# edge.net
KiCad netlist of a schematic drawn in EAGLE
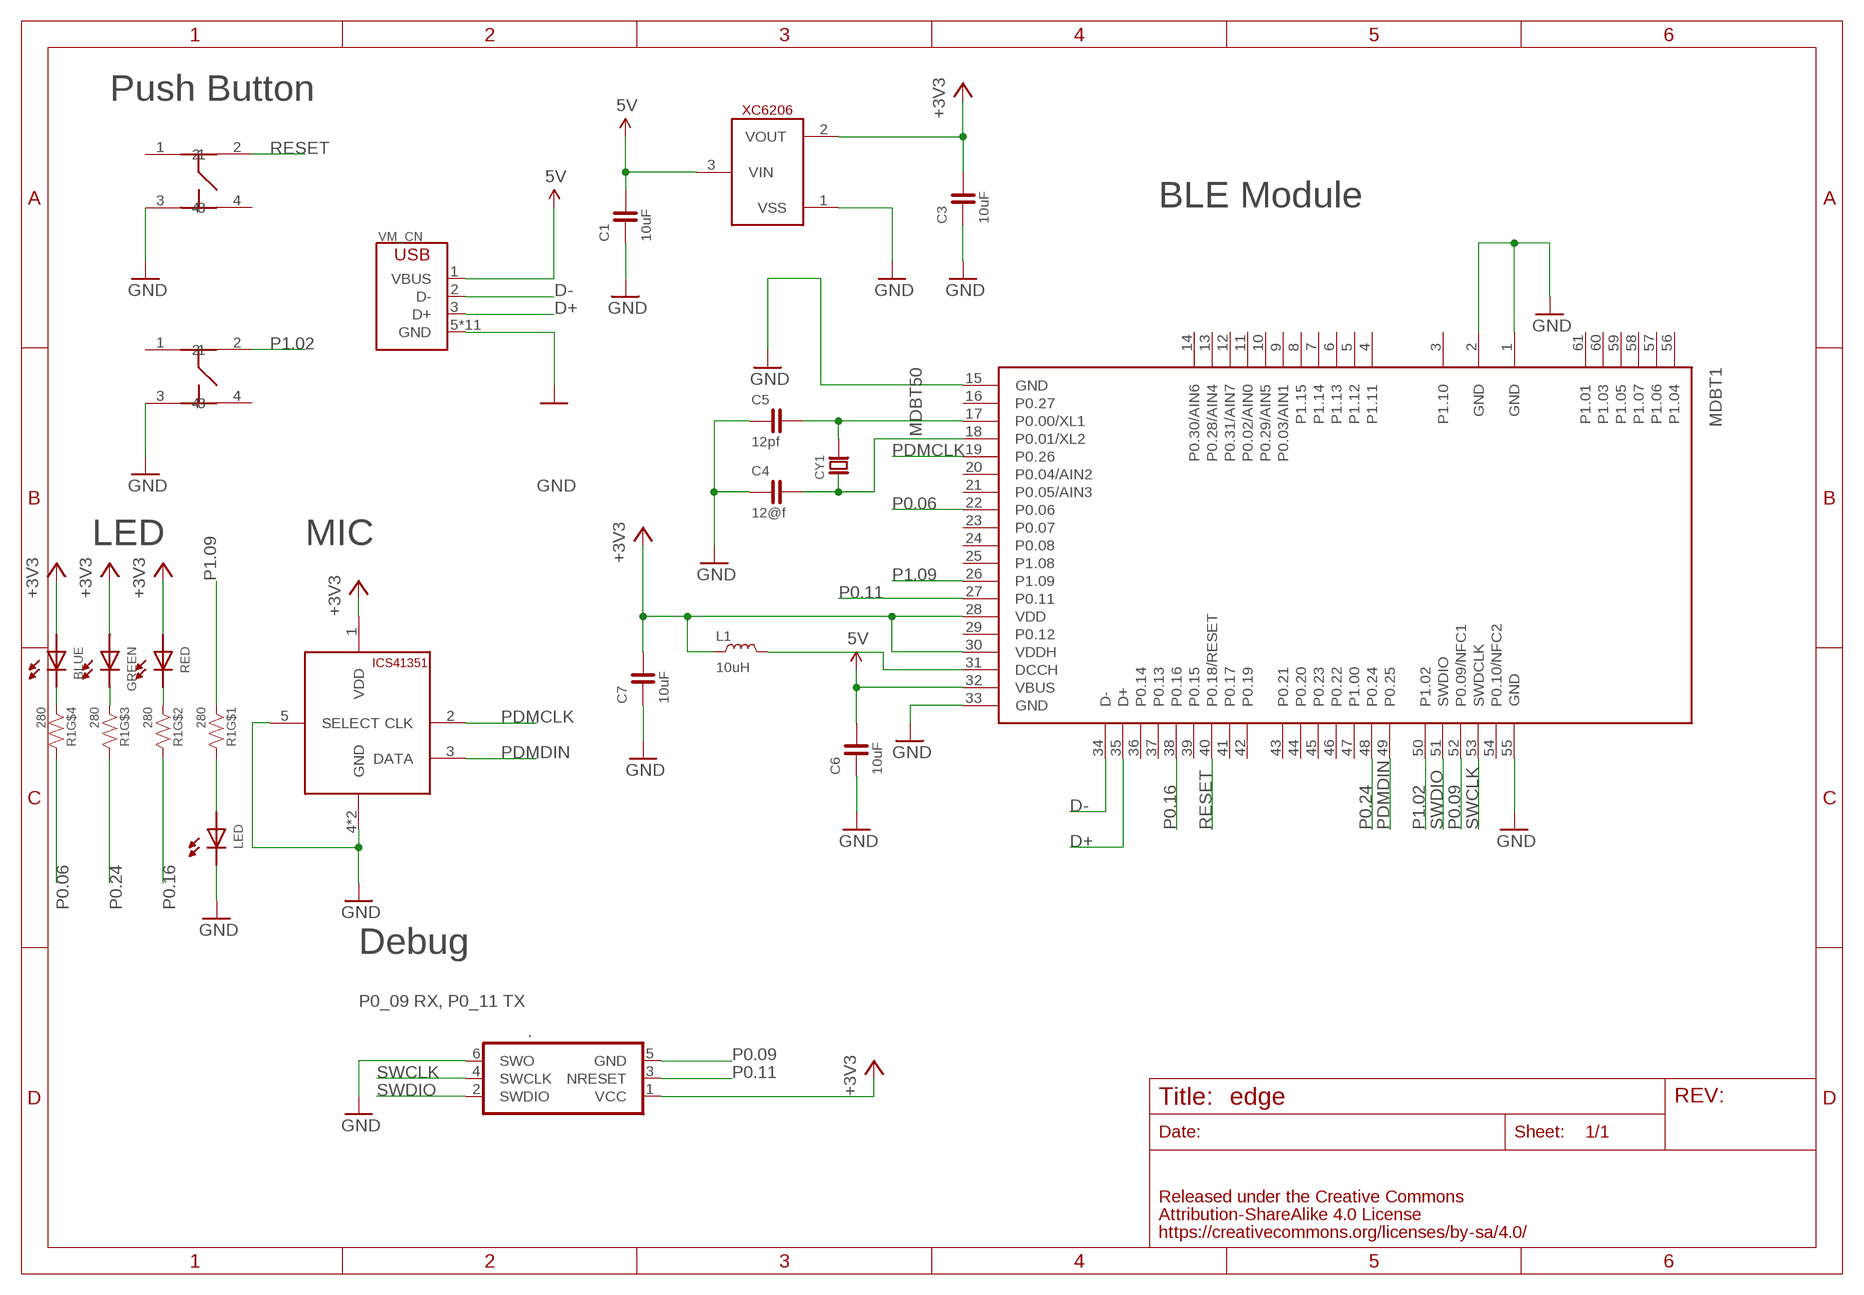
[diagram p0: schematic, sheet 1]

(export (version "E")
  (design (tool "Eeschema 10.0.6"))
  (components
    (comp (ref ".")
      (value "TC2030-IDC-NL")
      (footprint "eagle-import:TC2030-IDC-NL")
      (libsource (lib "eagle-import") (part "TC2030-IDC-NL"))
    )
    (comp (ref "BLUE")
      (value "LED-0603")
      (footprint "eagle-import:0603")
      (libsource (lib "eagle-import") (part "LED-0603"))
    )
    (comp (ref "C1")
      (value "10uF")
      (footprint "eagle-import:0603")
      (libsource (lib "eagle-import") (part "CAPACITOR-0603"))
    )
    (comp (ref "C3")
      (value "10uF")
      (footprint "eagle-import:0603")
      (libsource (lib "eagle-import") (part "CAPACITOR-0603"))
    )
    (comp (ref "C4")
      (value "12@f")
      (footprint "eagle-import:0603")
      (libsource (lib "eagle-import") (part "CAPACITOR-0603"))
    )
    (comp (ref "C5")
      (value "12pf")
      (footprint "eagle-import:0603")
      (libsource (lib "eagle-import") (part "CAPACITOR-0603"))
    )
    (comp (ref "C6")
      (value "10uF")
      (footprint "eagle-import:0603")
      (libsource (lib "eagle-import") (part "CAPACITOR-0603"))
    )
    (comp (ref "C7")
      (value "10uF")
      (footprint "eagle-import:0603")
      (libsource (lib "eagle-import") (part "CAPACITOR-0603"))
    )
    (comp (ref "CY1")
      (value "CRYSTAL-ABS07")
      (footprint "eagle-import:ABRACON-ABS07-32.768KHZ")
      (libsource (lib "eagle-import") (part "CRYSTAL-ABS07"))
    )
    (comp (ref "GREEN")
      (value "LED-0603")
      (footprint "eagle-import:0603")
      (libsource (lib "eagle-import") (part "LED-0603"))
    )
    (comp (ref "IC1")
      (value "XC6206")
      (footprint "eagle-import:SOT-23")
      (libsource (lib "eagle-import") (part "XC6206"))
    )
    (comp (ref "L1")
      (value "10uH")
      (footprint "eagle-import:0603")
      (libsource (lib "eagle-import") (part "COIL-0603"))
    )
    (comp (ref "LED")
      (value "LED-0603")
      (footprint "eagle-import:0603")
      (libsource (lib "eagle-import") (part "LED-0603"))
    )
    (comp (ref "MDBT1")
      (value "MDBT50")
      (footprint "eagle-import:MDBT50")
      (libsource (lib "eagle-import") (part "MDBT50"))
    )
    (comp (ref "MIC1")
      (value "TDK-ICS41351")
      (footprint "eagle-import:ICS41351")
      (libsource (lib "eagle-import") (part "TDK-ICS41351"))
    )
    (comp (ref "R1")
      (value "280")
      (footprint "eagle-import:EXBV8V")
      (libsource (lib "eagle-import") (part "RESISTOR_ARRAY"))
    )
    (comp (ref "RED")
      (value "LED-0603")
      (footprint "eagle-import:0603")
      (libsource (lib "eagle-import") (part "LED-0603"))
    )
    (comp (ref "U$1")
      (value "SWICTH-4P(KMR2)")
      (footprint "eagle-import:SWITCH-4P(KMR2)")
      (libsource (lib "eagle-import") (part "SWICTH-4P(KMR2)"))
    )
    (comp (ref "U$5")
      (value "SWICTH-4P(KMR2)")
      (footprint "eagle-import:SWITCH-4P(KMR2)")
      (libsource (lib "eagle-import") (part "SWICTH-4P(KMR2)"))
    )
    (comp (ref "VM_CN")
      (value "USB-ZX62D")
      (footprint "eagle-import:ZX62D-B-5PA8")
      (libsource (lib "eagle-import") (part "USB-ZX62D"))
    )
  )
  (nets
    (net (code "1") (name "+3V3") (class "Default")
      (node (ref ".") (pin "1") (pinfunction "VCC_1") (pintype "passive"))
      (node (ref "BLUE") (pin "ANODE") (pinfunction "ANODE_ANODE") (pintype "passive"))
      (node (ref "C3") (pin "2") (pinfunction "2_2") (pintype "passive"))
      (node (ref "C7") (pin "2") (pinfunction "2_2") (pintype "passive"))
      (node (ref "GREEN") (pin "ANODE") (pinfunction "ANODE_ANODE") (pintype "passive"))
      (node (ref "IC1") (pin "2") (pinfunction "VOUT_2") (pintype "bidirectional"))
      (node (ref "L1") (pin "1") (pinfunction "1_1") (pintype "bidirectional"))
      (node (ref "MDBT1") (pin "28") (pinfunction "VDD_28") (pintype "bidirectional"))
      (node (ref "MDBT1") (pin "30") (pinfunction "VDDH_30") (pintype "bidirectional"))
      (node (ref "MIC1") (pin "1") (pinfunction "VDD_1") (pintype "bidirectional"))
      (node (ref "RED") (pin "ANODE") (pinfunction "ANODE_ANODE") (pintype "passive"))
    )
    (net (code "2") (name "/D+") (class "Default")
      (node (ref "MDBT1") (pin "35") (pinfunction "D+_35") (pintype "bidirectional"))
      (node (ref "VM_CN") (pin "3") (pinfunction "D+_3") (pintype "bidirectional"))
    )
    (net (code "3") (name "/D-") (class "Default")
      (node (ref "MDBT1") (pin "34") (pinfunction "D-_34") (pintype "bidirectional"))
      (node (ref "VM_CN") (pin "2") (pinfunction "D-_2") (pintype "bidirectional"))
    )
    (net (code "4") (name "/P0.06") (class "Default")
      (node (ref "MDBT1") (pin "22") (pinfunction "P0.06_22") (pintype "bidirectional"))
      (node (ref "R1") (pin "5") (pinfunction "2_5") (pintype "bidirectional"))
    )
    (net (code "5") (name "/P0.09") (class "Default")
      (node (ref ".") (pin "5") (pinfunction "GND_5") (pintype "passive"))
      (node (ref "MDBT1") (pin "52") (pinfunction "P0.09/NFC1_52") (pintype "bidirectional"))
    )
    (net (code "6") (name "/P0.11") (class "Default")
      (node (ref ".") (pin "3") (pinfunction "NRESET_3") (pintype "passive"))
      (node (ref "MDBT1") (pin "27") (pinfunction "P0.11_27") (pintype "bidirectional"))
    )
    (net (code "7") (name "/P0.16") (class "Default")
      (node (ref "MDBT1") (pin "38") (pinfunction "P0.16_38") (pintype "bidirectional"))
      (node (ref "R1") (pin "7") (pinfunction "2_7") (pintype "bidirectional"))
    )
    (net (code "8") (name "/P0.24") (class "Default")
      (node (ref "MDBT1") (pin "48") (pinfunction "P0.24_48") (pintype "bidirectional"))
      (node (ref "R1") (pin "6") (pinfunction "2_6") (pintype "bidirectional"))
    )
    (net (code "9") (name "/P1.02") (class "Default")
      (node (ref "MDBT1") (pin "50") (pinfunction "P1.02_50") (pintype "bidirectional"))
      (node (ref "U$1") (pin "2") (pinfunction "2_2") (pintype "bidirectional"))
    )
    (net (code "10") (name "/P1.09") (class "Default")
      (node (ref "MDBT1") (pin "26") (pinfunction "P1.09_26") (pintype "bidirectional"))
      (node (ref "R1") (pin "1") (pinfunction "1_1") (pintype "bidirectional"))
    )
    (net (code "11") (name "/PDMCLK") (class "Default")
      (node (ref "MDBT1") (pin "19") (pinfunction "P0.26_19") (pintype "bidirectional"))
      (node (ref "MIC1") (pin "2") (pinfunction "CLK_2") (pintype "bidirectional"))
    )
    (net (code "12") (name "/PDMDIN") (class "Default")
      (node (ref "MDBT1") (pin "49") (pinfunction "P0.25_49") (pintype "bidirectional"))
      (node (ref "MIC1") (pin "3") (pinfunction "DATA_3") (pintype "bidirectional"))
    )
    (net (code "13") (name "/RESET") (class "Default")
      (node (ref "MDBT1") (pin "40") (pinfunction "P0.18/RESET_40") (pintype "bidirectional"))
      (node (ref "U$5") (pin "2") (pinfunction "2_2") (pintype "bidirectional"))
    )
    (net (code "14") (name "/SWCLK") (class "Default")
      (node (ref ".") (pin "4") (pinfunction "SWCLK_4") (pintype "passive"))
      (node (ref "MDBT1") (pin "53") (pinfunction "SWDCLK_53") (pintype "bidirectional"))
    )
    (net (code "15") (name "/SWDIO") (class "Default")
      (node (ref ".") (pin "2") (pinfunction "SWDIO_2") (pintype "passive"))
      (node (ref "MDBT1") (pin "51") (pinfunction "SWDIO_51") (pintype "bidirectional"))
    )
    (net (code "16") (name "5V") (class "Default")
      (node (ref "C1") (pin "2") (pinfunction "2_2") (pintype "passive"))
      (node (ref "C6") (pin "2") (pinfunction "2_2") (pintype "passive"))
      (node (ref "IC1") (pin "3") (pinfunction "VIN_3") (pintype "bidirectional"))
      (node (ref "MDBT1") (pin "32") (pinfunction "VBUS_32") (pintype "bidirectional"))
      (node (ref "VM_CN") (pin "1") (pinfunction "VBUS_1") (pintype "bidirectional"))
    )
    (net (code "17") (name "GND") (class "Default")
      (node (ref ".") (pin "6") (pinfunction "SWO_6") (pintype "passive"))
      (node (ref "C1") (pin "1") (pinfunction "1_1") (pintype "passive"))
      (node (ref "C3") (pin "1") (pinfunction "1_1") (pintype "passive"))
      (node (ref "C4") (pin "1") (pinfunction "1_1") (pintype "passive"))
      (node (ref "C5") (pin "1") (pinfunction "1_1") (pintype "passive"))
      (node (ref "C6") (pin "1") (pinfunction "1_1") (pintype "passive"))
      (node (ref "C7") (pin "1") (pinfunction "1_1") (pintype "passive"))
      (node (ref "IC1") (pin "1") (pinfunction "VSS_1") (pintype "bidirectional"))
      (node (ref "LED") (pin "CATHODE") (pinfunction "CATHODE_CATHODE") (pintype "passive"))
      (node (ref "MDBT1") (pin "1") (pinfunction "GND_1") (pintype "bidirectional"))
      (node (ref "MDBT1") (pin "15") (pinfunction "GND_15") (pintype "bidirectional"))
      (node (ref "MDBT1") (pin "2") (pinfunction "GND_2") (pintype "bidirectional"))
      (node (ref "MDBT1") (pin "33") (pinfunction "GND_33") (pintype "bidirectional"))
      (node (ref "MDBT1") (pin "55") (pinfunction "GND_55") (pintype "bidirectional"))
      (node (ref "MIC1") (pin "4") (pinfunction "GND_4") (pintype "bidirectional"))
      (node (ref "MIC1") (pin "5") (pinfunction "SELECT_5") (pintype "bidirectional"))
      (node (ref "MIC1") (pin "6") (pinfunction "GND_6") (pintype "bidirectional"))
      (node (ref "U$1") (pin "3") (pinfunction "3_3") (pintype "bidirectional"))
      (node (ref "U$5") (pin "3") (pinfunction "3_3") (pintype "bidirectional"))
      (node (ref "VM_CN") (pin "5") (pinfunction "GND_5") (pintype "bidirectional"))
      (node (ref "VM_CN") (pin "B1") (pinfunction "GND_B1") (pintype "bidirectional"))
      (node (ref "VM_CN") (pin "B2") (pinfunction "GND_B2") (pintype "bidirectional"))
      (node (ref "VM_CN") (pin "B3") (pinfunction "GND_B3") (pintype "bidirectional"))
      (node (ref "VM_CN") (pin "B4") (pinfunction "GND_B4") (pintype "bidirectional"))
      (node (ref "VM_CN") (pin "T1") (pinfunction "GND_T1") (pintype "bidirectional"))
      (node (ref "VM_CN") (pin "T2") (pinfunction "GND_T2") (pintype "bidirectional"))
      (node (ref "VM_CN") (pin "T3") (pinfunction "GND_T3") (pintype "bidirectional"))
      (node (ref "VM_CN") (pin "T4") (pinfunction "GND_T4") (pintype "bidirectional"))
      (node (ref "VM_CN") (pin "T5") (pinfunction "GND_T5") (pintype "bidirectional"))
      (node (ref "VM_CN") (pin "T6") (pinfunction "GND_T6") (pintype "bidirectional"))
    )
    (net (code "18") (name "Net-(MDBT1-DCCH)") (class "Default")
      (node (ref "L1") (pin "2") (pinfunction "2_2") (pintype "bidirectional"))
      (node (ref "MDBT1") (pin "31") (pinfunction "DCCH_31") (pintype "bidirectional"))
    )
    (net (code "19") (name "Net-(MDBT1-P0.00{slash}XL1)") (class "Default")
      (node (ref "C5") (pin "2") (pinfunction "2_2") (pintype "passive"))
      (node (ref "CY1") (pin "P$2") (pinfunction "P$2_P$2") (pintype "bidirectional"))
      (node (ref "MDBT1") (pin "17") (pinfunction "P0.00/XL1_17") (pintype "bidirectional"))
    )
    (net (code "20") (name "Net-(MDBT1-P0.01{slash}XL2)") (class "Default")
      (node (ref "C4") (pin "2") (pinfunction "2_2") (pintype "passive"))
      (node (ref "CY1") (pin "P$1") (pinfunction "P$1_P$1") (pintype "bidirectional"))
      (node (ref "MDBT1") (pin "18") (pinfunction "P0.01/XL2_18") (pintype "bidirectional"))
    )
    (net (code "21") (name "Net-(R1A-2)") (class "Default")
      (node (ref "LED") (pin "ANODE") (pinfunction "ANODE_ANODE") (pintype "passive"))
      (node (ref "R1") (pin "8") (pinfunction "2_8") (pintype "bidirectional"))
    )
    (net (code "22") (name "Net-(R1B-1)") (class "Default")
      (node (ref "R1") (pin "2") (pinfunction "1_2") (pintype "bidirectional"))
      (node (ref "RED") (pin "CATHODE") (pinfunction "CATHODE_CATHODE") (pintype "passive"))
    )
    (net (code "23") (name "Net-(R1C-1)") (class "Default")
      (node (ref "GREEN") (pin "CATHODE") (pinfunction "CATHODE_CATHODE") (pintype "passive"))
      (node (ref "R1") (pin "3") (pinfunction "1_3") (pintype "bidirectional"))
    )
    (net (code "24") (name "Net-(R1D-1)") (class "Default")
      (node (ref "BLUE") (pin "CATHODE") (pinfunction "CATHODE_CATHODE") (pintype "passive"))
      (node (ref "R1") (pin "4") (pinfunction "1_4") (pintype "bidirectional"))
    )
    (net (code "25") (name "unconnected-(MDBT1-P0.02{slash}AIN0-Pad11)") (class "Default")
      (node (ref "MDBT1") (pin "11") (pinfunction "P0.02/AIN0_11") (pintype "bidirectional"))
    )
    (net (code "26") (name "unconnected-(MDBT1-P0.03{slash}AIN1-Pad9)") (class "Default")
      (node (ref "MDBT1") (pin "9") (pinfunction "P0.03/AIN1_9") (pintype "bidirectional"))
    )
    (net (code "27") (name "unconnected-(MDBT1-P0.04{slash}AIN2-Pad20)") (class "Default")
      (node (ref "MDBT1") (pin "20") (pinfunction "P0.04/AIN2_20") (pintype "bidirectional"))
    )
    (net (code "28") (name "unconnected-(MDBT1-P0.05{slash}AIN3-Pad21)") (class "Default")
      (node (ref "MDBT1") (pin "21") (pinfunction "P0.05/AIN3_21") (pintype "bidirectional"))
    )
    (net (code "29") (name "unconnected-(MDBT1-P0.07-Pad23)") (class "Default")
      (node (ref "MDBT1") (pin "23") (pinfunction "P0.07_23") (pintype "bidirectional"))
    )
    (net (code "30") (name "unconnected-(MDBT1-P0.08-Pad24)") (class "Default")
      (node (ref "MDBT1") (pin "24") (pinfunction "P0.08_24") (pintype "bidirectional"))
    )
    (net (code "31") (name "unconnected-(MDBT1-P0.10{slash}NFC2-Pad54)") (class "Default")
      (node (ref "MDBT1") (pin "54") (pinfunction "P0.10/NFC2_54") (pintype "bidirectional"))
    )
    (net (code "32") (name "unconnected-(MDBT1-P0.12-Pad29)") (class "Default")
      (node (ref "MDBT1") (pin "29") (pinfunction "P0.12_29") (pintype "bidirectional"))
    )
    (net (code "33") (name "unconnected-(MDBT1-P0.13-Pad37)") (class "Default")
      (node (ref "MDBT1") (pin "37") (pinfunction "P0.13_37") (pintype "bidirectional"))
    )
    (net (code "34") (name "unconnected-(MDBT1-P0.14-Pad36)") (class "Default")
      (node (ref "MDBT1") (pin "36") (pinfunction "P0.14_36") (pintype "bidirectional"))
    )
    (net (code "35") (name "unconnected-(MDBT1-P0.15-Pad39)") (class "Default")
      (node (ref "MDBT1") (pin "39") (pinfunction "P0.15_39") (pintype "bidirectional"))
    )
    (net (code "36") (name "unconnected-(MDBT1-P0.17-Pad41)") (class "Default")
      (node (ref "MDBT1") (pin "41") (pinfunction "P0.17_41") (pintype "bidirectional"))
    )
    (net (code "37") (name "unconnected-(MDBT1-P0.19-Pad42)") (class "Default")
      (node (ref "MDBT1") (pin "42") (pinfunction "P0.19_42") (pintype "bidirectional"))
    )
    (net (code "38") (name "unconnected-(MDBT1-P0.20-Pad44)") (class "Default")
      (node (ref "MDBT1") (pin "44") (pinfunction "P0.20_44") (pintype "bidirectional"))
    )
    (net (code "39") (name "unconnected-(MDBT1-P0.21-Pad43)") (class "Default")
      (node (ref "MDBT1") (pin "43") (pinfunction "P0.21_43") (pintype "bidirectional"))
    )
    (net (code "40") (name "unconnected-(MDBT1-P0.22-Pad46)") (class "Default")
      (node (ref "MDBT1") (pin "46") (pinfunction "P0.22_46") (pintype "bidirectional"))
    )
    (net (code "41") (name "unconnected-(MDBT1-P0.23-Pad45)") (class "Default")
      (node (ref "MDBT1") (pin "45") (pinfunction "P0.23_45") (pintype "bidirectional"))
    )
    (net (code "42") (name "unconnected-(MDBT1-P0.27-Pad16)") (class "Default")
      (node (ref "MDBT1") (pin "16") (pinfunction "P0.27_16") (pintype "bidirectional"))
    )
    (net (code "43") (name "unconnected-(MDBT1-P0.28{slash}AIN4-Pad13)") (class "Default")
      (node (ref "MDBT1") (pin "13") (pinfunction "P0.28/AIN4_13") (pintype "bidirectional"))
    )
    (net (code "44") (name "unconnected-(MDBT1-P0.29{slash}AIN5-Pad10)") (class "Default")
      (node (ref "MDBT1") (pin "10") (pinfunction "P0.29/AIN5_10") (pintype "bidirectional"))
    )
    (net (code "45") (name "unconnected-(MDBT1-P0.30{slash}AIN6-Pad14)") (class "Default")
      (node (ref "MDBT1") (pin "14") (pinfunction "P0.30/AIN6_14") (pintype "bidirectional"))
    )
    (net (code "46") (name "unconnected-(MDBT1-P0.31{slash}AIN7-Pad12)") (class "Default")
      (node (ref "MDBT1") (pin "12") (pinfunction "P0.31/AIN7_12") (pintype "bidirectional"))
    )
    (net (code "47") (name "unconnected-(MDBT1-P1.00-Pad47)") (class "Default")
      (node (ref "MDBT1") (pin "47") (pinfunction "P1.00_47") (pintype "bidirectional"))
    )
    (net (code "48") (name "unconnected-(MDBT1-P1.01-Pad61)") (class "Default")
      (node (ref "MDBT1") (pin "61") (pinfunction "P1.01_61") (pintype "bidirectional"))
    )
    (net (code "49") (name "unconnected-(MDBT1-P1.03-Pad60)") (class "Default")
      (node (ref "MDBT1") (pin "60") (pinfunction "P1.03_60") (pintype "bidirectional"))
    )
    (net (code "50") (name "unconnected-(MDBT1-P1.04-Pad56)") (class "Default")
      (node (ref "MDBT1") (pin "56") (pinfunction "P1.04_56") (pintype "bidirectional"))
    )
    (net (code "51") (name "unconnected-(MDBT1-P1.05-Pad59)") (class "Default")
      (node (ref "MDBT1") (pin "59") (pinfunction "P1.05_59") (pintype "bidirectional"))
    )
    (net (code "52") (name "unconnected-(MDBT1-P1.06-Pad57)") (class "Default")
      (node (ref "MDBT1") (pin "57") (pinfunction "P1.06_57") (pintype "bidirectional"))
    )
    (net (code "53") (name "unconnected-(MDBT1-P1.07-Pad58)") (class "Default")
      (node (ref "MDBT1") (pin "58") (pinfunction "P1.07_58") (pintype "bidirectional"))
    )
    (net (code "54") (name "unconnected-(MDBT1-P1.08-Pad25)") (class "Default")
      (node (ref "MDBT1") (pin "25") (pinfunction "P1.08_25") (pintype "bidirectional"))
    )
    (net (code "55") (name "unconnected-(MDBT1-P1.10-Pad3)") (class "Default")
      (node (ref "MDBT1") (pin "3") (pinfunction "P1.10_3") (pintype "bidirectional"))
    )
    (net (code "56") (name "unconnected-(MDBT1-P1.11-Pad4)") (class "Default")
      (node (ref "MDBT1") (pin "4") (pinfunction "P1.11_4") (pintype "bidirectional"))
    )
    (net (code "57") (name "unconnected-(MDBT1-P1.12-Pad5)") (class "Default")
      (node (ref "MDBT1") (pin "5") (pinfunction "P1.12_5") (pintype "bidirectional"))
    )
    (net (code "58") (name "unconnected-(MDBT1-P1.13-Pad6)") (class "Default")
      (node (ref "MDBT1") (pin "6") (pinfunction "P1.13_6") (pintype "bidirectional"))
    )
    (net (code "59") (name "unconnected-(MDBT1-P1.14-Pad7)") (class "Default")
      (node (ref "MDBT1") (pin "7") (pinfunction "P1.14_7") (pintype "bidirectional"))
    )
    (net (code "60") (name "unconnected-(MDBT1-P1.15-Pad8)") (class "Default")
      (node (ref "MDBT1") (pin "8") (pinfunction "P1.15_8") (pintype "bidirectional"))
    )
    (net (code "61") (name "unconnected-(U$1-Pad1)") (class "Default")
      (node (ref "U$1") (pin "1") (pinfunction "1_1") (pintype "bidirectional"))
    )
    (net (code "62") (name "unconnected-(U$1-Pad4)") (class "Default")
      (node (ref "U$1") (pin "4") (pinfunction "4_4") (pintype "bidirectional"))
    )
    (net (code "63") (name "unconnected-(U$5-Pad1)") (class "Default")
      (node (ref "U$5") (pin "1") (pinfunction "1_1") (pintype "bidirectional"))
    )
    (net (code "64") (name "unconnected-(U$5-Pad4)") (class "Default")
      (node (ref "U$5") (pin "4") (pinfunction "4_4") (pintype "bidirectional"))
    )
  )
)
